# LMS.net
KiCad netlist of a schematic drawn in Altium Designer
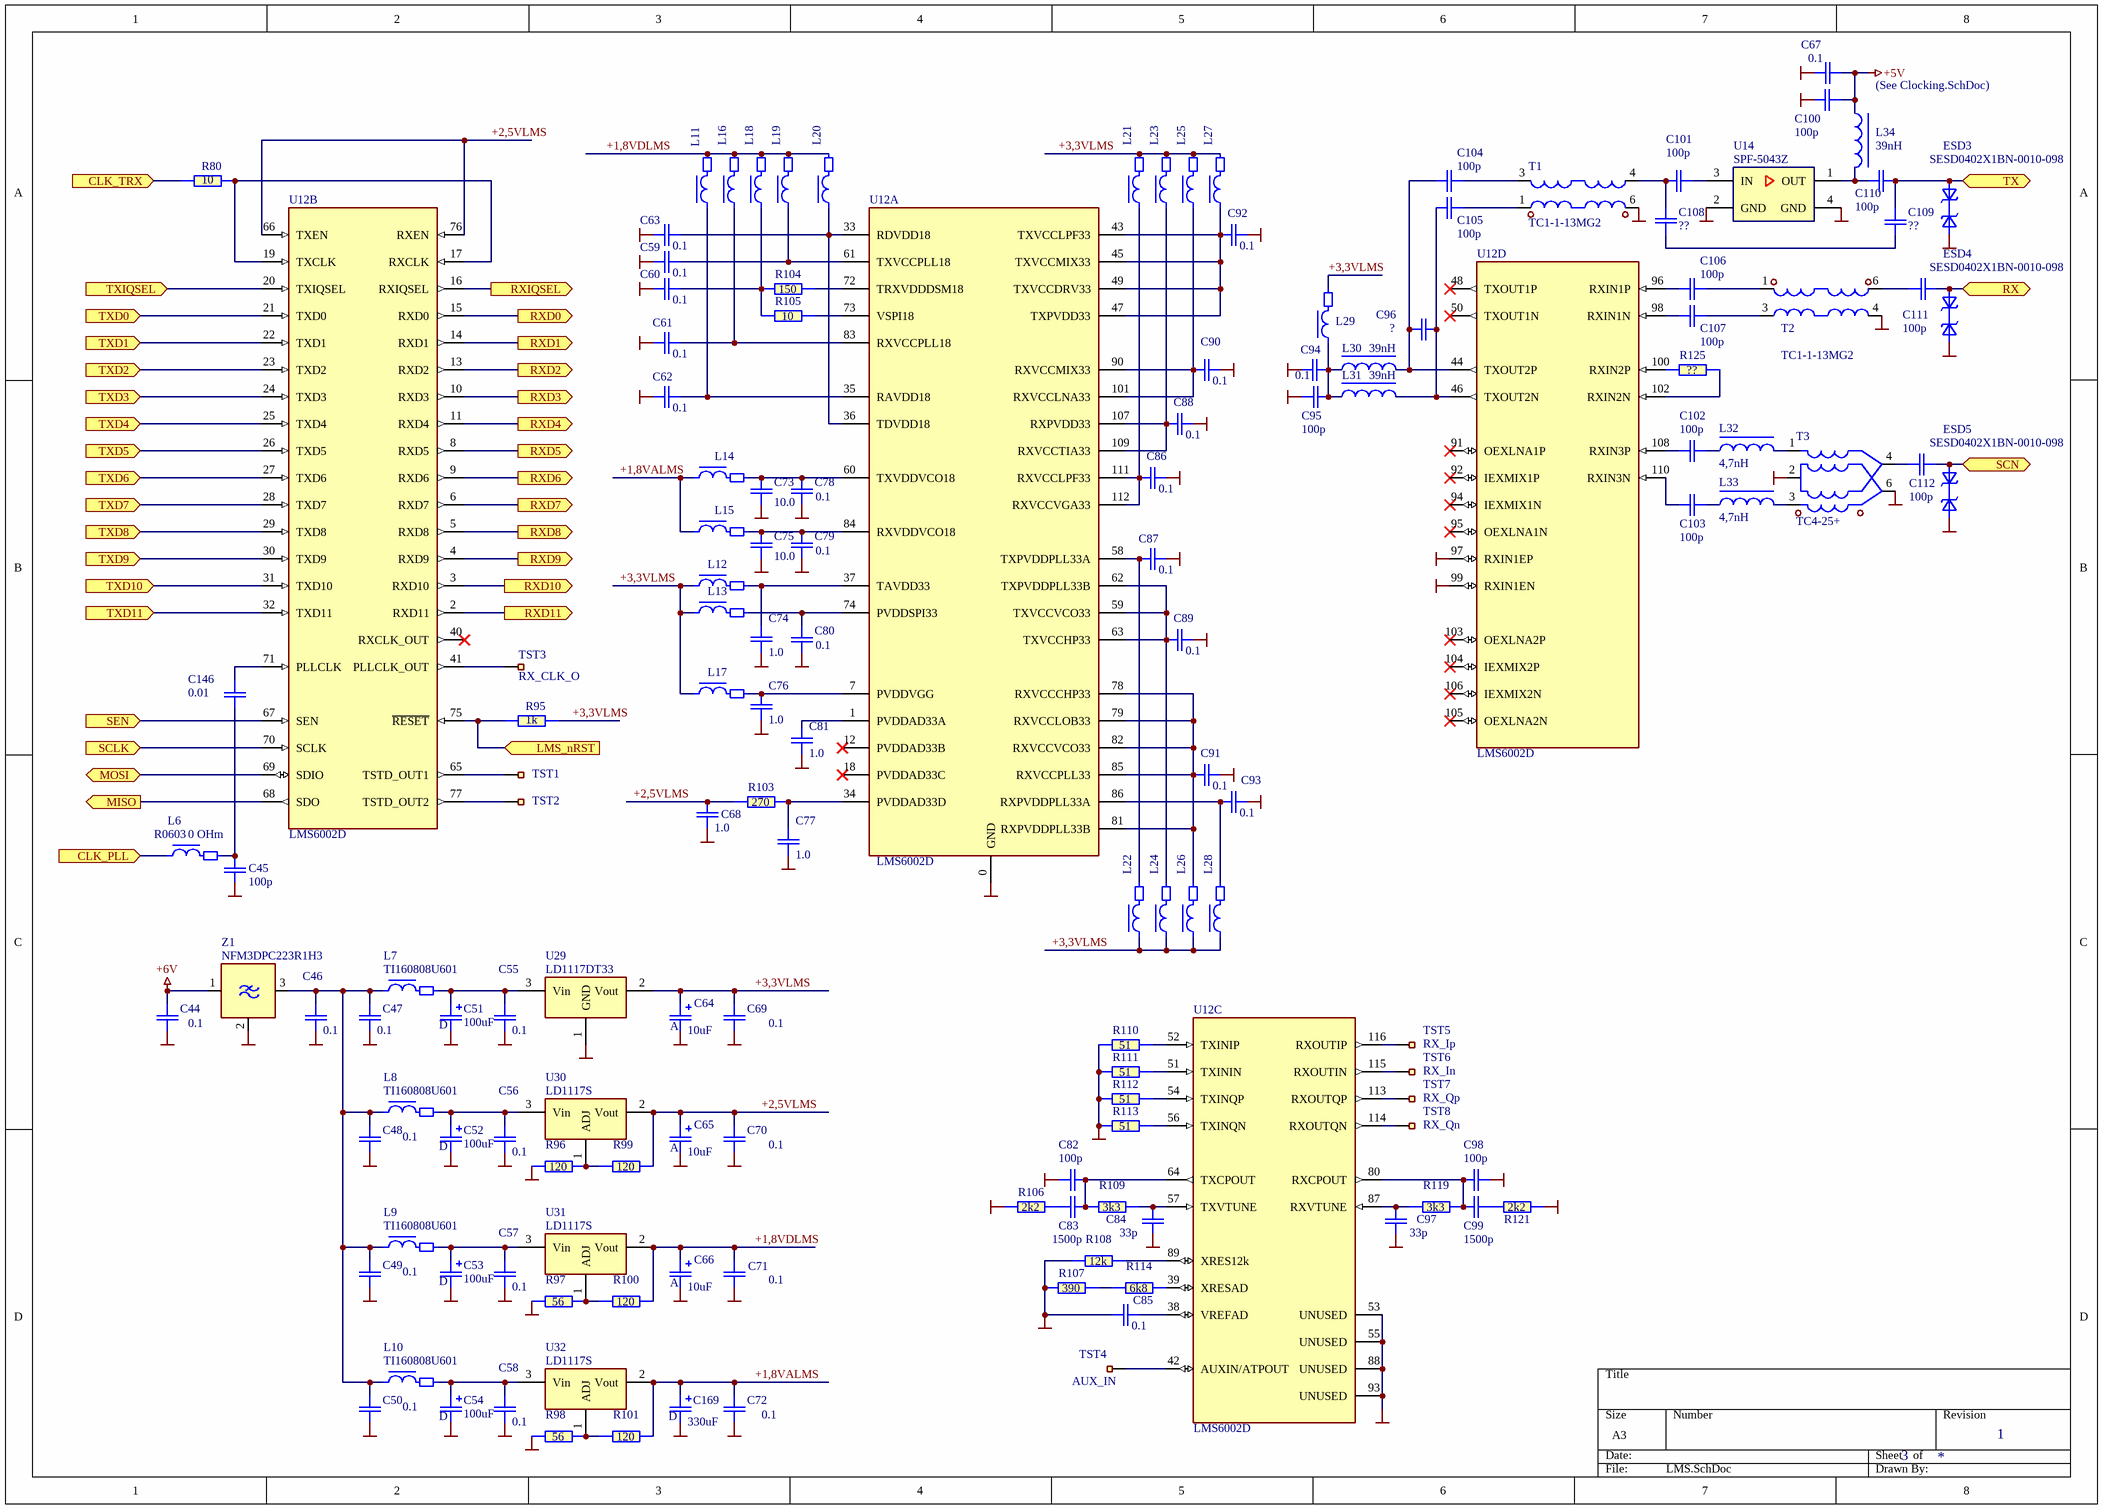
[diagram p0: LMS.SchDoc]

(export (version "E")
  (design (tool "Eeschema 10.0.6"))
  (components
    (comp (ref "C44")
      (value "0.1")
      (footprint "C0402-Phillips")
      (description "Конденсатор")
      (fields (field (name "MANUFACTURER") "MURATA") (field (name "TOLERANCE") "20%"))
      (libsource (lib "Capacitors") (part "C0402"))
    )
    (comp (ref "C45")
      (value "100p")
      (footprint "C0603-PHILLIPS")
      (description "Конденсатор")
      (fields (field (name "MANUFACTURER") "MURATA") (field (name "TOLERANCE") "20%"))
      (libsource (lib "altium-import") (part "root_2_mirrored_C0603_"))
    )
    (comp (ref "C46")
      (value "0.1")
      (footprint "C0402-Phillips")
      (description "Конденсатор")
      (fields (field (name "MANUFACTURER") "MURATA") (field (name "TOLERANCE") "20%"))
      (libsource (lib "Capacitors") (part "C0402"))
    )
    (comp (ref "C47")
      (value "0.1")
      (footprint "C0402-Phillips")
      (description "Конденсатор")
      (fields (field (name "MANUFACTURER") "MURATA") (field (name "TOLERANCE") "20%"))
      (libsource (lib "Capacitors") (part "C0402"))
    )
    (comp (ref "C48")
      (value "0.1")
      (footprint "C0402-Phillips")
      (description "Конденсатор")
      (fields (field (name "MANUFACTURER") "MURATA") (field (name "TOLERANCE") "20%"))
      (libsource (lib "Capacitors") (part "C0402"))
    )
    (comp (ref "C49")
      (value "0.1")
      (footprint "C0402-Phillips")
      (description "Конденсатор")
      (fields (field (name "MANUFACTURER") "MURATA") (field (name "TOLERANCE") "20%"))
      (libsource (lib "Capacitors") (part "C0402"))
    )
    (comp (ref "C50")
      (value "0.1")
      (footprint "C0402-Phillips")
      (description "Конденсатор")
      (fields (field (name "MANUFACTURER") "MURATA") (field (name "TOLERANCE") "20%"))
      (libsource (lib "Capacitors") (part "C0402"))
    )
    (comp (ref "C51")
      (value "100uF")
      (footprint "cd7343")
      (description "Конденсатор")
      (fields (field (name "MANUFACTURER") "SPRAGUE"))
      (libsource (lib "altium-import") (part "root_0_CD7343_"))
    )
    (comp (ref "C52")
      (value "100uF")
      (footprint "cd7343")
      (description "Конденсатор")
      (fields (field (name "MANUFACTURER") "SPRAGUE"))
      (libsource (lib "altium-import") (part "root_0_CD7343_"))
    )
    (comp (ref "C53")
      (value "100uF")
      (footprint "cd7343")
      (description "Конденсатор")
      (fields (field (name "MANUFACTURER") "SPRAGUE"))
      (libsource (lib "altium-import") (part "root_0_CD7343_"))
    )
    (comp (ref "C54")
      (value "100uF")
      (footprint "cd7343")
      (description "Конденсатор")
      (fields (field (name "MANUFACTURER") "SPRAGUE"))
      (libsource (lib "altium-import") (part "root_0_CD7343_"))
    )
    (comp (ref "C55")
      (value "0.1")
      (footprint "C0402-Phillips")
      (description "Конденсатор")
      (fields (field (name "MANUFACTURER") "MURATA") (field (name "TOLERANCE") "20%"))
      (libsource (lib "Capacitors") (part "C0402"))
    )
    (comp (ref "C56")
      (value "0.1")
      (footprint "C0402-Phillips")
      (description "Конденсатор")
      (fields (field (name "MANUFACTURER") "MURATA") (field (name "TOLERANCE") "20%"))
      (libsource (lib "Capacitors") (part "C0402"))
    )
    (comp (ref "C57")
      (value "0.1")
      (footprint "C0402-Phillips")
      (description "Конденсатор")
      (fields (field (name "MANUFACTURER") "MURATA") (field (name "TOLERANCE") "20%"))
      (libsource (lib "Capacitors") (part "C0402"))
    )
    (comp (ref "C58")
      (value "0.1")
      (footprint "C0402-Phillips")
      (description "Конденсатор")
      (fields (field (name "MANUFACTURER") "MURATA") (field (name "TOLERANCE") "20%"))
      (libsource (lib "Capacitors") (part "C0402"))
    )
    (comp (ref "C59")
      (value "0.1")
      (footprint "C0402-Phillips")
      (description "Конденсатор")
      (fields (field (name "MANUFACTURER") "MURATA") (field (name "TOLERANCE") "20%"))
      (libsource (lib "Capacitors") (part "C0402"))
    )
    (comp (ref "C60")
      (value "0.1")
      (footprint "C0402-Phillips")
      (description "Конденсатор")
      (fields (field (name "MANUFACTURER") "MURATA") (field (name "TOLERANCE") "20%"))
      (libsource (lib "Capacitors") (part "C0402"))
    )
    (comp (ref "C61")
      (value "0.1")
      (footprint "C0402-Phillips")
      (description "Конденсатор")
      (fields (field (name "MANUFACTURER") "MURATA") (field (name "TOLERANCE") "20%"))
      (libsource (lib "Capacitors") (part "C0402"))
    )
    (comp (ref "C62")
      (value "0.1")
      (footprint "C0402-Phillips")
      (description "Конденсатор")
      (fields (field (name "MANUFACTURER") "MURATA") (field (name "TOLERANCE") "20%"))
      (libsource (lib "Capacitors") (part "C0402"))
    )
    (comp (ref "C63")
      (value "0.1")
      (footprint "C0402-Phillips")
      (description "Конденсатор")
      (fields (field (name "MANUFACTURER") "MURATA") (field (name "TOLERANCE") "20%"))
      (libsource (lib "Capacitors") (part "C0402"))
    )
    (comp (ref "C64")
      (value "10uF")
      (footprint "CA3216")
      (description "Конденсатор")
      (fields (field (name "MANUFACTURER") "SPRAGUE"))
      (libsource (lib "Capacitors") (part "CA3216"))
    )
    (comp (ref "C65")
      (value "10uF")
      (footprint "CA3216")
      (description "Конденсатор")
      (fields (field (name "MANUFACTURER") "SPRAGUE"))
      (libsource (lib "Capacitors") (part "CA3216"))
    )
    (comp (ref "C66")
      (value "10uF")
      (footprint "CA3216")
      (description "Конденсатор")
      (fields (field (name "MANUFACTURER") "SPRAGUE"))
      (libsource (lib "Capacitors") (part "CA3216"))
    )
    (comp (ref "C67")
      (value "0.1")
      (footprint "C0402-Phillips")
      (description "Конденсатор")
      (fields (field (name "MANUFACTURER") "MURATA") (field (name "TOLERANCE") "20%"))
      (libsource (lib "Capacitors") (part "C0402"))
    )
    (comp (ref "C68")
      (value "1.0")
      (footprint "C0603-PHILLIPS")
      (description "Конденсатор")
      (fields (field (name "MANUFACTURER") "MURATA") (field (name "TOLERANCE") "20%"))
      (libsource (lib "altium-import") (part "root_0_C0603_"))
    )
    (comp (ref "C69")
      (value "0.1")
      (footprint "C0402-Phillips")
      (description "Конденсатор")
      (fields (field (name "MANUFACTURER") "MURATA") (field (name "TOLERANCE") "20%"))
      (libsource (lib "Capacitors") (part "C0402"))
    )
    (comp (ref "C70")
      (value "0.1")
      (footprint "C0402-Phillips")
      (description "Конденсатор")
      (fields (field (name "MANUFACTURER") "MURATA") (field (name "TOLERANCE") "20%"))
      (libsource (lib "Capacitors") (part "C0402"))
    )
    (comp (ref "C71")
      (value "0.1")
      (footprint "C0402-Phillips")
      (description "Конденсатор")
      (fields (field (name "MANUFACTURER") "MURATA") (field (name "TOLERANCE") "20%"))
      (libsource (lib "Capacitors") (part "C0402"))
    )
    (comp (ref "C72")
      (value "0.1")
      (footprint "C0402-Phillips")
      (description "Конденсатор")
      (fields (field (name "MANUFACTURER") "MURATA") (field (name "TOLERANCE") "20%"))
      (libsource (lib "Capacitors") (part "C0402"))
    )
    (comp (ref "C73")
      (value "10.0")
      (footprint "C0603-Phillips")
      (description "Конденсатор")
      (fields (field (name "MANUFACTURER") "MURATA") (field (name "TOLERANCE") "20%"))
      (libsource (lib "Capacitors") (part "C0603"))
    )
    (comp (ref "C74")
      (value "1.0")
      (footprint "C0603-PHILLIPS")
      (description "Конденсатор")
      (fields (field (name "MANUFACTURER") "MURATA") (field (name "TOLERANCE") "20%"))
      (libsource (lib "altium-import") (part "root_0_C0603_"))
    )
    (comp (ref "C75")
      (value "10.0")
      (footprint "C0603-Phillips")
      (description "Конденсатор")
      (fields (field (name "MANUFACTURER") "MURATA") (field (name "TOLERANCE") "20%"))
      (libsource (lib "Capacitors") (part "C0603"))
    )
    (comp (ref "C76")
      (value "1.0")
      (footprint "C0603-PHILLIPS")
      (description "Конденсатор")
      (fields (field (name "MANUFACTURER") "MURATA") (field (name "TOLERANCE") "20%"))
      (libsource (lib "altium-import") (part "root_0_C0603_"))
    )
    (comp (ref "C77")
      (value "1.0")
      (footprint "C0603-PHILLIPS")
      (description "Конденсатор")
      (fields (field (name "MANUFACTURER") "MURATA") (field (name "TOLERANCE") "20%"))
      (libsource (lib "altium-import") (part "root_0_C0603_"))
    )
    (comp (ref "C78")
      (value "0.1")
      (footprint "C0402-Phillips")
      (description "Конденсатор")
      (fields (field (name "MANUFACTURER") "MURATA") (field (name "TOLERANCE") "20%"))
      (libsource (lib "Capacitors") (part "C0402"))
    )
    (comp (ref "C79")
      (value "0.1")
      (footprint "C0402-cirq")
      (description "Конденсатор")
      (fields (field (name "MANUFACTURER") "MURATA") (field (name "TOLERANCE") "20%"))
      (libsource (lib "Capacitors") (part "C0402"))
    )
    (comp (ref "C80")
      (value "0.1")
      (footprint "C0402-cirq")
      (description "Конденсатор")
      (fields (field (name "MANUFACTURER") "MURATA") (field (name "TOLERANCE") "20%"))
      (libsource (lib "Capacitors") (part "C0402"))
    )
    (comp (ref "C81")
      (value "1.0")
      (footprint "C0603-PHILLIPS")
      (description "Конденсатор")
      (fields (field (name "MANUFACTURER") "MURATA") (field (name "TOLERANCE") "20%"))
      (libsource (lib "altium-import") (part "root_0_C0603_"))
    )
    (comp (ref "C82")
      (value "100p")
      (footprint "C0603-PHILLIPS")
      (description "Конденсатор")
      (fields (field (name "MANUFACTURER") "MURATA") (field (name "TOLERANCE") "20%"))
      (libsource (lib "altium-import") (part "root_1_mirrored_C0603_"))
    )
    (comp (ref "C83")
      (value "1500p")
      (footprint "C0603-PHILLIPS")
      (description "Конденсатор")
      (fields (field (name "MANUFACTURER") "MURATA") (field (name "TOLERANCE") "20%"))
      (libsource (lib "altium-import") (part "root_1_mirrored_C0603_"))
    )
    (comp (ref "C84")
      (value "33p")
      (footprint "C0603-PHILLIPS")
      (description "Конденсатор")
      (fields (field (name "MANUFACTURER") "MURATA") (field (name "TOLERANCE") "20%"))
      (libsource (lib "altium-import") (part "root_2_mirrored_C0603_"))
    )
    (comp (ref "C85")
      (value "0.1")
      (footprint "C0402-Phillips")
      (description "Конденсатор")
      (fields (field (name "MANUFACTURER") "MURATA") (field (name "TOLERANCE") "20%"))
      (libsource (lib "Capacitors") (part "C0402"))
    )
    (comp (ref "C86")
      (value "0.1")
      (footprint "C0402-Phillips")
      (description "Конденсатор")
      (fields (field (name "MANUFACTURER") "MURATA") (field (name "TOLERANCE") "20%"))
      (libsource (lib "Capacitors") (part "C0402"))
    )
    (comp (ref "C87")
      (value "0.1")
      (footprint "C0402-Phillips")
      (description "Конденсатор")
      (fields (field (name "MANUFACTURER") "MURATA") (field (name "TOLERANCE") "20%"))
      (libsource (lib "Capacitors") (part "C0402"))
    )
    (comp (ref "C88")
      (value "0.1")
      (footprint "C0402-cirq")
      (description "Конденсатор")
      (fields (field (name "MANUFACTURER") "MURATA") (field (name "TOLERANCE") "20%"))
      (libsource (lib "Capacitors") (part "C0402"))
    )
    (comp (ref "C89")
      (value "0.1")
      (footprint "C0402-cirq")
      (description "Конденсатор")
      (fields (field (name "MANUFACTURER") "MURATA") (field (name "TOLERANCE") "20%"))
      (libsource (lib "Capacitors") (part "C0402"))
    )
    (comp (ref "C90")
      (value "0.1")
      (footprint "C0402-Phillips")
      (description "Конденсатор")
      (fields (field (name "MANUFACTURER") "MURATA") (field (name "TOLERANCE") "20%"))
      (libsource (lib "Capacitors") (part "C0402"))
    )
    (comp (ref "C91")
      (value "0.1")
      (footprint "C0402-Phillips")
      (description "Конденсатор")
      (fields (field (name "MANUFACTURER") "MURATA") (field (name "TOLERANCE") "20%"))
      (libsource (lib "Capacitors") (part "C0402"))
    )
    (comp (ref "C92")
      (value "0.1")
      (footprint "C0402-cirq")
      (description "Конденсатор")
      (fields (field (name "MANUFACTURER") "MURATA") (field (name "TOLERANCE") "20%"))
      (libsource (lib "Capacitors") (part "C0402"))
    )
    (comp (ref "C93")
      (value "0.1")
      (footprint "C0402-Phillips")
      (description "Конденсатор")
      (fields (field (name "MANUFACTURER") "MURATA") (field (name "TOLERANCE") "20%"))
      (libsource (lib "Capacitors") (part "C0402"))
    )
    (comp (ref "C94")
      (value "0.1")
      (footprint "C0402-Phillips")
      (description "Конденсатор")
      (fields (field (name "MANUFACTURER") "MURATA") (field (name "TOLERANCE") "20%"))
      (libsource (lib "Capacitors") (part "C0402"))
    )
    (comp (ref "C95")
      (value "100p")
      (footprint "C0603-PHILLIPS")
      (description "Конденсатор")
      (fields (field (name "MANUFACTURER") "MURATA") (field (name "TOLERANCE") "20%"))
      (libsource (lib "altium-import") (part "root_3_C0603_"))
    )
    (comp (ref "C96")
      (value "?")
      (footprint "C0603-PHILLIPS")
      (description "Конденсатор")
      (fields (field (name "MANUFACTURER") "MURATA") (field (name "TOLERANCE") "20%"))
      (libsource (lib "altium-import") (part "root_3_C0603_"))
    )
    (comp (ref "C97")
      (value "33p")
      (footprint "C0603-PHILLIPS")
      (description "Конденсатор")
      (fields (field (name "MANUFACTURER") "MURATA") (field (name "TOLERANCE") "20%"))
      (libsource (lib "altium-import") (part "root_2_C0603_"))
    )
    (comp (ref "C98")
      (value "100p")
      (footprint "C0603-PHILLIPS")
      (description "Конденсатор")
      (fields (field (name "MANUFACTURER") "MURATA") (field (name "TOLERANCE") "20%"))
      (libsource (lib "altium-import") (part "root_1_C0603_"))
    )
    (comp (ref "C99")
      (value "1500p")
      (footprint "C0603-PHILLIPS")
      (description "Конденсатор")
      (fields (field (name "MANUFACTURER") "MURATA") (field (name "TOLERANCE") "20%"))
      (libsource (lib "altium-import") (part "root_1_C0603_"))
    )
    (comp (ref "C100")
      (value "100p")
      (footprint "C0603-PHILLIPS")
      (description "Конденсатор")
      (fields (field (name "MANUFACTURER") "MURATA") (field (name "TOLERANCE") "20%"))
      (libsource (lib "altium-import") (part "root_1_C0603_"))
    )
    (comp (ref "C101")
      (value "100p")
      (footprint "C0603-PHILLIPS")
      (description "Конденсатор")
      (fields (field (name "MANUFACTURER") "MURATA") (field (name "TOLERANCE") "20%"))
      (libsource (lib "altium-import") (part "root_1_C0603_"))
    )
    (comp (ref "C102")
      (value "100p")
      (footprint "C0603-PHILLIPS")
      (description "Конденсатор")
      (fields (field (name "MANUFACTURER") "MURATA") (field (name "TOLERANCE") "20%"))
      (libsource (lib "altium-import") (part "root_1_C0603_"))
    )
    (comp (ref "C103")
      (value "100p")
      (footprint "C0603-PHILLIPS")
      (description "Конденсатор")
      (fields (field (name "MANUFACTURER") "MURATA") (field (name "TOLERANCE") "20%"))
      (libsource (lib "altium-import") (part "root_1_C0603_"))
    )
    (comp (ref "C104")
      (value "100p")
      (footprint "C0603-PHILLIPS")
      (description "Конденсатор")
      (fields (field (name "MANUFACTURER") "MURATA") (field (name "TOLERANCE") "20%"))
      (libsource (lib "altium-import") (part "root_1_C0603_"))
    )
    (comp (ref "C105")
      (value "100p")
      (footprint "C0603-PHILLIPS")
      (description "Конденсатор")
      (fields (field (name "MANUFACTURER") "MURATA") (field (name "TOLERANCE") "20%"))
      (libsource (lib "altium-import") (part "root_1_C0603_"))
    )
    (comp (ref "C106")
      (value "100p")
      (footprint "C0603-PHILLIPS")
      (description "Конденсатор")
      (fields (field (name "MANUFACTURER") "MURATA") (field (name "TOLERANCE") "20%"))
      (libsource (lib "altium-import") (part "root_1_C0603_"))
    )
    (comp (ref "C107")
      (value "100p")
      (footprint "C0603-PHILLIPS")
      (description "Конденсатор")
      (fields (field (name "MANUFACTURER") "MURATA") (field (name "TOLERANCE") "20%"))
      (libsource (lib "altium-import") (part "root_1_C0603_"))
    )
    (comp (ref "C108")
      (value "??")
      (footprint "C0603-PHILLIPS")
      (description "Конденсатор")
      (fields (field (name "MANUFACTURER") "MURATA") (field (name "TOLERANCE") "20%"))
      (libsource (lib "altium-import") (part "root_0_C0603_"))
    )
    (comp (ref "C109")
      (value "??")
      (footprint "C0603-PHILLIPS")
      (description "Конденсатор")
      (fields (field (name "MANUFACTURER") "MURATA") (field (name "TOLERANCE") "20%"))
      (libsource (lib "altium-import") (part "root_2_C0603_"))
    )
    (comp (ref "C110")
      (value "100p")
      (footprint "C0603-PHILLIPS")
      (description "Конденсатор")
      (fields (field (name "MANUFACTURER") "MURATA") (field (name "TOLERANCE") "20%"))
      (libsource (lib "altium-import") (part "root_1_C0603_"))
    )
    (comp (ref "C111")
      (value "100p")
      (footprint "C0603-PHILLIPS")
      (description "Конденсатор")
      (fields (field (name "MANUFACTURER") "MURATA") (field (name "TOLERANCE") "20%"))
      (libsource (lib "altium-import") (part "root_3_C0603_"))
    )
    (comp (ref "C112")
      (value "100p")
      (footprint "C0603-PHILLIPS")
      (description "Конденсатор")
      (fields (field (name "MANUFACTURER") "MURATA") (field (name "TOLERANCE") "20%"))
      (libsource (lib "altium-import") (part "root_1_C0603_"))
    )
    (comp (ref "C146")
      (value "0.01")
      (footprint "C0603-PHILLIPS")
      (description "Конденсатор")
      (fields (field (name "MANUFACTURER") "MURATA") (field (name "TOLERANCE") "20%"))
      (libsource (lib "altium-import") (part "root_2_mirrored_C0603_"))
    )
    (comp (ref "C169")
      (value "330uF")
      (footprint "cd7343")
      (description "Конденсатор")
      (fields (field (name "MANUFACTURER") "Kemet"))
      (libsource (lib "altium-import") (part "root_0_CD7343_"))
    )
    (comp (ref "ESD3")
      (value "SESD0402X1BN-0010-098")
      (footprint "R0402-Phillips")
      (description "ESD diod bi-directional")
      (fields (field (name "MANUFACTURER") "Tyco Electronics Corp"))
      (libsource (lib "*") (part "SESD0402X"))
    )
    (comp (ref "ESD4")
      (value "SESD0402X1BN-0010-098")
      (footprint "R0402-Phillips")
      (description "ESD diod bi-directional")
      (fields (field (name "MANUFACTURER") "Tyco Electronics Corp"))
      (libsource (lib "*") (part "SESD0402X"))
    )
    (comp (ref "ESD5")
      (value "SESD0402X1BN-0010-098")
      (footprint "R0402-Phillips")
      (description "ESD diod bi-directional")
      (fields (field (name "MANUFACTURER") "Tyco Electronics Corp"))
      (libsource (lib "*") (part "SESD0402X"))
    )
    (comp (ref "L6")
      (value "R0603")
      (footprint "Andy:Ti160808-Phillips")
      (description "Дроссель ЭМС")
      (fields (field (name "MANUFACTURER") "MURATA") (field (name "ALTIUM_VALUE") "0 OHm"))
      (libsource (lib "altium-import") (part "root_0_TI160808_"))
    )
    (comp (ref "L7")
      (value "TI160808U601")
      (footprint "Andy:Ti160808-Phillips")
      (description "Дроссель ЭМС")
      (fields (field (name "MANUFACTURER") "MURATA"))
      (libsource (lib "altium-import") (part "root_0_TI160808_"))
    )
    (comp (ref "L8")
      (value "TI160808U601")
      (footprint "Andy:Ti160808-Phillips")
      (description "Дроссель ЭМС")
      (fields (field (name "MANUFACTURER") "MURATA"))
      (libsource (lib "altium-import") (part "root_0_TI160808_"))
    )
    (comp (ref "L9")
      (value "TI160808U601")
      (footprint "Andy:Ti160808-Phillips")
      (description "Дроссель ЭМС")
      (fields (field (name "MANUFACTURER") "MURATA"))
      (libsource (lib "altium-import") (part "root_0_TI160808_"))
    )
    (comp (ref "L10")
      (value "TI160808U601")
      (footprint "Andy:Ti160808-Phillips")
      (description "Дроссель ЭМС")
      (fields (field (name "MANUFACTURER") "MURATA"))
      (libsource (lib "altium-import") (part "root_0_TI160808_"))
    )
    (comp (ref "L11")
      (value "TI160808U601")
      (footprint "Andy:Ti160808-Phillips")
      (description "Дроссель ЭМС")
      (fields (field (name "MANUFACTURER") "MURATA"))
      (libsource (lib "altium-import") (part "root_1_TI160808_"))
    )
    (comp (ref "L12")
      (value "TI160808U601")
      (footprint "Andy:Ti160808-Phillips")
      (description "Дроссель ЭМС")
      (fields (field (name "MANUFACTURER") "MURATA"))
      (libsource (lib "altium-import") (part "root_0_TI160808_"))
    )
    (comp (ref "L13")
      (value "TI160808U601")
      (footprint "Andy:Ti160808-Phillips")
      (description "Дроссель ЭМС")
      (fields (field (name "MANUFACTURER") "MURATA"))
      (libsource (lib "altium-import") (part "root_0_TI160808_"))
    )
    (comp (ref "L14")
      (value "TI160808U601")
      (footprint "Andy:Ti160808-Phillips")
      (description "Дроссель ЭМС")
      (fields (field (name "MANUFACTURER") "MURATA"))
      (libsource (lib "altium-import") (part "root_0_TI160808_"))
    )
    (comp (ref "L15")
      (value "TI160808U601")
      (footprint "Andy:Ti160808-Phillips")
      (description "Дроссель ЭМС")
      (fields (field (name "MANUFACTURER") "MURATA"))
      (libsource (lib "altium-import") (part "root_0_TI160808_"))
    )
    (comp (ref "L16")
      (value "TI160808U601")
      (footprint "Andy:Ti160808-Phillips")
      (description "Дроссель ЭМС")
      (fields (field (name "MANUFACTURER") "MURATA"))
      (libsource (lib "altium-import") (part "root_1_TI160808_"))
    )
    (comp (ref "L17")
      (value "TI160808U601")
      (footprint "Andy:Ti160808-Phillips")
      (description "Дроссель ЭМС")
      (fields (field (name "MANUFACTURER") "MURATA"))
      (libsource (lib "altium-import") (part "root_0_TI160808_"))
    )
    (comp (ref "L18")
      (value "TI160808U601")
      (footprint "Andy:Ti160808-Phillips")
      (description "Дроссель ЭМС")
      (fields (field (name "MANUFACTURER") "MURATA"))
      (libsource (lib "altium-import") (part "root_1_TI160808_"))
    )
    (comp (ref "L19")
      (value "TI160808U601")
      (footprint "Andy:Ti160808-Phillips")
      (description "Дроссель ЭМС")
      (fields (field (name "MANUFACTURER") "MURATA"))
      (libsource (lib "altium-import") (part "root_1_TI160808_"))
    )
    (comp (ref "L20")
      (value "TI160808U601")
      (footprint "Andy:Ti160808-Phillips")
      (description "Дроссель ЭМС")
      (fields (field (name "MANUFACTURER") "MURATA"))
      (libsource (lib "altium-import") (part "root_1_TI160808_"))
    )
    (comp (ref "L21")
      (value "TI160808U601")
      (footprint "Andy:Ti160808-Phillips")
      (description "Дроссель ЭМС")
      (fields (field (name "MANUFACTURER") "MURATA"))
      (libsource (lib "altium-import") (part "root_1_TI160808_"))
    )
    (comp (ref "L22")
      (value "TI160808U601")
      (footprint "Andy:Ti160808-Phillips")
      (description "Дроссель ЭМС")
      (fields (field (name "MANUFACTURER") "MURATA"))
      (libsource (lib "altium-import") (part "root_1_TI160808_"))
    )
    (comp (ref "L23")
      (value "TI160808U601")
      (footprint "Andy:Ti160808-Phillips")
      (description "Дроссель ЭМС")
      (fields (field (name "MANUFACTURER") "MURATA"))
      (libsource (lib "altium-import") (part "root_1_TI160808_"))
    )
    (comp (ref "L24")
      (value "TI160808U601")
      (footprint "Andy:Ti160808-Phillips")
      (description "Дроссель ЭМС")
      (fields (field (name "MANUFACTURER") "MURATA"))
      (libsource (lib "altium-import") (part "root_1_TI160808_"))
    )
    (comp (ref "L25")
      (value "TI160808U601")
      (footprint "Andy:Ti160808-Phillips")
      (description "Дроссель ЭМС")
      (fields (field (name "MANUFACTURER") "MURATA"))
      (libsource (lib "altium-import") (part "root_1_TI160808_"))
    )
    (comp (ref "L26")
      (value "TI160808U601")
      (footprint "Andy:Ti160808-Phillips")
      (description "Дроссель ЭМС")
      (fields (field (name "MANUFACTURER") "MURATA"))
      (libsource (lib "altium-import") (part "root_1_TI160808_"))
    )
    (comp (ref "L27")
      (value "TI160808U601")
      (footprint "Andy:Ti160808-Phillips")
      (description "Дроссель ЭМС")
      (fields (field (name "MANUFACTURER") "MURATA"))
      (libsource (lib "altium-import") (part "root_1_TI160808_"))
    )
    (comp (ref "L28")
      (value "TI160808U601")
      (footprint "Andy:Ti160808-Phillips")
      (description "Дроссель ЭМС")
      (fields (field (name "MANUFACTURER") "MURATA"))
      (libsource (lib "altium-import") (part "root_1_TI160808_"))
    )
    (comp (ref "L29")
      (value "TI160808U601")
      (footprint "Andy:Ti160808-Phillips")
      (description "Дроссель ЭМС")
      (fields (field (name "MANUFACTURER") "MURATA"))
      (libsource (lib "altium-import") (part "root_1_TI160808_"))
    )
    (comp (ref "L30")
      (value "39nH")
      (footprint "Andy:TF160808-Phillips")
      (description "Индуктивность")
      (fields (field (name "MANUFACTURER") "SMD"))
      (libsource (lib "altium-import") (part "root_0_TF160808_"))
    )
    (comp (ref "L31")
      (value "39nH")
      (footprint "Andy:TF160808-Phillips")
      (description "Индуктивность")
      (fields (field (name "MANUFACTURER") "SMD"))
      (libsource (lib "altium-import") (part "root_0_TF160808_"))
    )
    (comp (ref "L32")
      (value "4,7nH")
      (footprint "Andy:TF160808-Phillips")
      (description "Индуктивность")
      (fields (field (name "MANUFACTURER") "SMD"))
      (libsource (lib "altium-import") (part "root_0_TF160808_"))
    )
    (comp (ref "L33")
      (value "4,7nH")
      (footprint "Andy:TF160808-Phillips")
      (description "Индуктивность")
      (fields (field (name "MANUFACTURER") "SMD"))
      (libsource (lib "altium-import") (part "root_0_TF160808_"))
    )
    (comp (ref "L34")
      (value "39nH")
      (footprint "Andy:TF160808-Phillips")
      (description "Индуктивность")
      (fields (field (name "MANUFACTURER") "SMD"))
      (libsource (lib "altium-import") (part "root_3_TF160808_"))
    )
    (comp (ref "R80")
      (value "10")
      (footprint "R0603-PHILLIPS")
      (description "Резистор")
      (fields (field (name "MANUFACTURER") "YAGEO") (field (name "TOLERANCE") "5%"))
      (libsource (lib "altium-import") (part "root_1_R0603_"))
    )
    (comp (ref "R95")
      (value "1k")
      (footprint "R0603-PHILLIPS")
      (description "Резистор")
      (fields (field (name "MANUFACTURER") "YAGEO") (field (name "TOLERANCE") "5%"))
      (libsource (lib "altium-import") (part "root_1_R0603_"))
    )
    (comp (ref "R96")
      (value "120")
      (footprint "R0603-PHILLIPS")
      (description "Резистор")
      (fields (field (name "MANUFACTURER") "YAGEO") (field (name "TOLERANCE") "5%"))
      (libsource (lib "altium-import") (part "root_1_R0603_"))
    )
    (comp (ref "R97")
      (value "56")
      (footprint "R0603-PHILLIPS")
      (description "Резистор")
      (fields (field (name "MANUFACTURER") "YAGEO") (field (name "TOLERANCE") "5%"))
      (libsource (lib "altium-import") (part "root_1_R0603_"))
    )
    (comp (ref "R98")
      (value "56")
      (footprint "R0603-PHILLIPS")
      (description "Резистор")
      (fields (field (name "MANUFACTURER") "YAGEO") (field (name "TOLERANCE") "5%"))
      (libsource (lib "altium-import") (part "root_1_R0603_"))
    )
    (comp (ref "R99")
      (value "120")
      (footprint "R0603-PHILLIPS")
      (description "Резистор")
      (fields (field (name "MANUFACTURER") "YAGEO") (field (name "TOLERANCE") "5%"))
      (libsource (lib "altium-import") (part "root_1_R0603_"))
    )
    (comp (ref "R100")
      (value "120")
      (footprint "R0603-PHILLIPS")
      (description "Резистор")
      (fields (field (name "MANUFACTURER") "YAGEO") (field (name "TOLERANCE") "5%"))
      (libsource (lib "altium-import") (part "root_1_R0603_"))
    )
    (comp (ref "R101")
      (value "120")
      (footprint "R0603-PHILLIPS")
      (description "Резистор")
      (fields (field (name "MANUFACTURER") "YAGEO") (field (name "TOLERANCE") "5%"))
      (libsource (lib "altium-import") (part "root_1_R0603_"))
    )
    (comp (ref "R103")
      (value "270")
      (footprint "R0603-PHILLIPS")
      (description "Резистор")
      (fields (field (name "MANUFACTURER") "YAGEO") (field (name "TOLERANCE") "5%"))
      (libsource (lib "altium-import") (part "root_1_R0603_"))
    )
    (comp (ref "R104")
      (value "150")
      (footprint "R0603-PHILLIPS")
      (description "Резистор")
      (fields (field (name "MANUFACTURER") "YAGEO") (field (name "TOLERANCE") "5%"))
      (libsource (lib "altium-import") (part "root_1_R0603_"))
    )
    (comp (ref "R105")
      (value "10")
      (footprint "R0603-PHILLIPS")
      (description "Резистор")
      (fields (field (name "MANUFACTURER") "YAGEO") (field (name "TOLERANCE") "5%"))
      (libsource (lib "altium-import") (part "root_1_R0603_"))
    )
    (comp (ref "R106")
      (value "2k2")
      (footprint "R0603-PHILLIPS")
      (description "Резистор")
      (fields (field (name "MANUFACTURER") "YAGEO") (field (name "TOLERANCE") "5%"))
      (libsource (lib "altium-import") (part "root_1_R0603_"))
    )
    (comp (ref "R107")
      (value "390")
      (footprint "R0603-PHILLIPS")
      (description "Резистор")
      (fields (field (name "MANUFACTURER") "YAGEO") (field (name "TOLERANCE") "5%"))
      (libsource (lib "altium-import") (part "root_1_R0603_"))
    )
    (comp (ref "R108")
      (value "12k")
      (footprint "R0603-PHILLIPS")
      (description "Резистор")
      (fields (field (name "MANUFACTURER") "YAGEO") (field (name "TOLERANCE") "5%"))
      (libsource (lib "altium-import") (part "root_1_R0603_"))
    )
    (comp (ref "R109")
      (value "3k3")
      (footprint "R0603-PHILLIPS")
      (description "Резистор")
      (fields (field (name "MANUFACTURER") "YAGEO") (field (name "TOLERANCE") "5%"))
      (libsource (lib "altium-import") (part "root_1_R0603_"))
    )
    (comp (ref "R110")
      (value "51")
      (footprint "R0603-PHILLIPS")
      (description "Резистор")
      (fields (field (name "MANUFACTURER") "YAGEO") (field (name "TOLERANCE") "5%"))
      (libsource (lib "altium-import") (part "root_1_R0603_"))
    )
    (comp (ref "R111")
      (value "51")
      (footprint "R0603-PHILLIPS")
      (description "Резистор")
      (fields (field (name "MANUFACTURER") "YAGEO") (field (name "TOLERANCE") "5%"))
      (libsource (lib "altium-import") (part "root_1_R0603_"))
    )
    (comp (ref "R112")
      (value "51")
      (footprint "R0603-PHILLIPS")
      (description "Резистор")
      (fields (field (name "MANUFACTURER") "YAGEO") (field (name "TOLERANCE") "5%"))
      (libsource (lib "altium-import") (part "root_1_R0603_"))
    )
    (comp (ref "R113")
      (value "51")
      (footprint "R0603-PHILLIPS")
      (description "Резистор")
      (fields (field (name "MANUFACTURER") "YAGEO") (field (name "TOLERANCE") "5%"))
      (libsource (lib "altium-import") (part "root_1_R0603_"))
    )
    (comp (ref "R114")
      (value "6k8")
      (footprint "R0603-PHILLIPS")
      (description "Резистор")
      (fields (field (name "MANUFACTURER") "YAGEO") (field (name "TOLERANCE") "5%"))
      (libsource (lib "altium-import") (part "root_1_R0603_"))
    )
    (comp (ref "R119")
      (value "3k3")
      (footprint "R0603-PHILLIPS")
      (description "Резистор")
      (fields (field (name "MANUFACTURER") "YAGEO") (field (name "TOLERANCE") "5%"))
      (libsource (lib "altium-import") (part "root_1_R0603_"))
    )
    (comp (ref "R121")
      (value "2k2")
      (footprint "R0603-PHILLIPS")
      (description "Резистор")
      (fields (field (name "MANUFACTURER") "YAGEO") (field (name "TOLERANCE") "5%"))
      (libsource (lib "altium-import") (part "root_1_R0603_"))
    )
    (comp (ref "R125")
      (value "??")
      (footprint "R0603-PHILLIPS")
      (description "Резистор")
      (fields (field (name "MANUFACTURER") "YAGEO") (field (name "TOLERANCE") "5%"))
      (libsource (lib "altium-import") (part "root_1_R0603_"))
    )
    (comp (ref "T1")
      (value "TC1-1-13MG2")
      (footprint "AT224-1")
      (description "Трансформатор")
      (fields (field (name "MANUFACTURER") "Mini-Cirquits"))
      (libsource (lib "Inductance Transformers") (part "TC1-1-13"))
    )
    (comp (ref "T2")
      (value "TC1-1-13MG2")
      (footprint "AT224-1")
      (description "Трансформатор")
      (fields (field (name "MANUFACTURER") "Mini-Cirquits"))
      (libsource (lib "") (part "TC1-1-13_1"))
    )
    (comp (ref "T3")
      (value "TC4-25+")
      (footprint "AT224-1")
      (description "Трансформатор")
      (fields (field (name "MANUFACTURER") "Mini-Cirquits"))
      (libsource (lib "Inductance Transformers") (part "TC4-25"))
    )
    (comp (ref "TST1")
      (value "~")
      (footprint "kp40x40")
      (description "Контактна  площадка")
      (fields (field (name "MANUFACTURER") "Конструктив"))
      (libsource (lib "Connectors") (part "KP"))
    )
    (comp (ref "TST2")
      (value "~")
      (footprint "kp40x40")
      (description "Контактна  площадка")
      (fields (field (name "MANUFACTURER") "Конструктив"))
      (libsource (lib "Connectors") (part "KP"))
    )
    (comp (ref "TST3")
      (value "RX_CLK_O")
      (footprint "kp40x40")
      (description "Контактна  площадка")
      (fields (field (name "MANUFACTURER") "Конструктив"))
      (libsource (lib "Connectors") (part "KP"))
    )
    (comp (ref "TST4")
      (value "AUX_IN")
      (footprint "kp40x40")
      (description "Контактна  площадка")
      (fields (field (name "MANUFACTURER") "Конструктив"))
      (libsource (lib "") (part "KP_1"))
    )
    (comp (ref "TST5")
      (value "RX_Ip")
      (footprint "kp40x40")
      (description "Контактна  площадка")
      (fields (field (name "MANUFACTURER") "Конструктив"))
      (libsource (lib "Connectors") (part "KP"))
    )
    (comp (ref "TST6")
      (value "RX_In")
      (footprint "kp40x40")
      (description "Контактна  площадка")
      (fields (field (name "MANUFACTURER") "Конструктив"))
      (libsource (lib "Connectors") (part "KP"))
    )
    (comp (ref "TST7")
      (value "RX_Qp")
      (footprint "kp40x40")
      (description "Контактна  площадка")
      (fields (field (name "MANUFACTURER") "Конструктив"))
      (libsource (lib "Connectors") (part "KP"))
    )
    (comp (ref "TST8")
      (value "RX_Qn")
      (footprint "kp40x40")
      (description "Контактна  площадка")
      (fields (field (name "MANUFACTURER") "Конструктив"))
      (libsource (lib "Connectors") (part "KP"))
    )
    (comp (ref "U12")
      (value "LMS6002D")
      (footprint "DQFN120(9x9/0.5mm)")
      (description "Микросхема")
      (fields (field (name "MANUFACTURER") "Lime Microsystems"))
      (libsource (lib "Andy") (part "LMS6002D"))
    )
    (comp (ref "U14")
      (value "SPF-5043Z")
      (footprint "SOT-343[2X1.25]")
      (description "Микросхема")
      (fields (field (name "MANUFACTURER") "RFMD"))
      (libsource (lib "MicroCircuitsM-Z") (part "SPF-5043Z"))
    )
    (comp (ref "U29")
      (value "LD1117DT33")
      (footprint "Foot3-4pins:to-252")
      (description "Микросхема")
      (fields (field (name "MANUFACTURER") "STMicro"))
      (libsource (lib "altium-import") (part "root_0_LD1117FIX_"))
    )
    (comp (ref "U30")
      (value "LD1117S")
      (footprint "Foot3-4pins:SOT-223-1")
      (description "Микросхема")
      (fields (field (name "MANUFACTURER") "STMicro"))
      (libsource (lib "altium-import") (part "root_0_LD1117ADJ_"))
    )
    (comp (ref "U31")
      (value "LD1117S")
      (footprint "Foot3-4pins:SOT-223-1")
      (description "Микросхема")
      (fields (field (name "MANUFACTURER") "STMicro"))
      (libsource (lib "altium-import") (part "root_0_LD1117ADJ_"))
    )
    (comp (ref "U32")
      (value "LD1117S")
      (footprint "Foot3-4pins:SOT-223-1")
      (description "Микросхема")
      (fields (field (name "MANUFACTURER") "STMicro"))
      (libsource (lib "altium-import") (part "root_0_LD1117ADJ_"))
    )
    (comp (ref "Z1")
      (value "NFM3DPC223R1H3")
      (footprint "NFM3DP")
      (description "Фильтр")
      (fields (field (name "MANUFACTURER") "Murata"))
      (libsource (lib "altium-import") (part "root_0_NFM3DP_"))
    )
  )
  (nets
    (net (code "1") (name "+5V") (class "Default")
      (node (ref "C100") (pin "2") (pinfunction "2_2") (pintype "passive"))
      (node (ref "C67") (pin "2") (pinfunction "2_2") (pintype "passive"))
      (node (ref "L34") (pin "1") (pinfunction "1_1") (pintype "passive"))
    )
    (net (code "2") (name "+6V") (class "Default")
      (node (ref "C44") (pin "1") (pinfunction "1_1") (pintype "passive"))
      (node (ref "Z1") (pin "1") (pinfunction "1_1") (pintype "passive"))
    )
    (net (code "3") (name "/+1,8VALMS") (class "Default")
      (node (ref "C169") (pin "1") (pinfunction "+_1") (pintype "passive"))
      (node (ref "C72") (pin "1") (pinfunction "1_1") (pintype "passive"))
      (node (ref "L14") (pin "1") (pinfunction "1_1") (pintype "passive"))
      (node (ref "L15") (pin "1") (pinfunction "1_1") (pintype "passive"))
      (node (ref "R101") (pin "2") (pinfunction "2_2") (pintype "passive"))
      (node (ref "U32") (pin "2") (pinfunction "Vout_2") (pintype "passive"))
    )
    (net (code "4") (name "/+1,8VDLMS") (class "Default")
      (node (ref "C66") (pin "1") (pinfunction "+_1") (pintype "passive"))
      (node (ref "C71") (pin "1") (pinfunction "1_1") (pintype "passive"))
      (node (ref "L11") (pin "2") (pinfunction "2_2") (pintype "passive"))
      (node (ref "L16") (pin "2") (pinfunction "2_2") (pintype "passive"))
      (node (ref "L18") (pin "2") (pinfunction "2_2") (pintype "passive"))
      (node (ref "L19") (pin "2") (pinfunction "2_2") (pintype "passive"))
      (node (ref "L20") (pin "2") (pinfunction "2_2") (pintype "passive"))
      (node (ref "R100") (pin "2") (pinfunction "2_2") (pintype "passive"))
      (node (ref "U31") (pin "2") (pinfunction "Vout_2") (pintype "passive"))
    )
    (net (code "5") (name "/+2,5VLMS") (class "Default")
      (node (ref "C65") (pin "1") (pinfunction "+_1") (pintype "passive"))
      (node (ref "C68") (pin "1") (pinfunction "1_1") (pintype "passive"))
      (node (ref "C70") (pin "1") (pinfunction "1_1") (pintype "passive"))
      (node (ref "R103") (pin "1") (pinfunction "1_1") (pintype "passive"))
      (node (ref "R99") (pin "2") (pinfunction "2_2") (pintype "passive"))
      (node (ref "U12") (pin "66") (pinfunction "TXEN_66") (pintype "input"))
      (node (ref "U12") (pin "76") (pinfunction "RXEN_76") (pintype "input"))
      (node (ref "U30") (pin "2") (pinfunction "Vout_2") (pintype "passive"))
    )
    (net (code "6") (name "/+3,3VLMS") (class "Default")
      (node (ref "C64") (pin "1") (pinfunction "+_1") (pintype "passive"))
      (node (ref "C69") (pin "1") (pinfunction "1_1") (pintype "passive"))
      (node (ref "L12") (pin "1") (pinfunction "1_1") (pintype "passive"))
      (node (ref "L13") (pin "1") (pinfunction "1_1") (pintype "passive"))
      (node (ref "L17") (pin "1") (pinfunction "1_1") (pintype "passive"))
      (node (ref "L21") (pin "2") (pinfunction "2_2") (pintype "passive"))
      (node (ref "L22") (pin "1") (pinfunction "1_1") (pintype "passive"))
      (node (ref "L23") (pin "2") (pinfunction "2_2") (pintype "passive"))
      (node (ref "L24") (pin "1") (pinfunction "1_1") (pintype "passive"))
      (node (ref "L25") (pin "2") (pinfunction "2_2") (pintype "passive"))
      (node (ref "L26") (pin "1") (pinfunction "1_1") (pintype "passive"))
      (node (ref "L27") (pin "2") (pinfunction "2_2") (pintype "passive"))
      (node (ref "L28") (pin "1") (pinfunction "1_1") (pintype "passive"))
      (node (ref "L29") (pin "2") (pinfunction "2_2") (pintype "passive"))
      (node (ref "R95") (pin "2") (pinfunction "2_2") (pintype "passive"))
      (node (ref "U29") (pin "2") (pinfunction "Vout_2") (pintype "passive"))
    )
    (net (code "7") (name "/CLK_PLL") (class "Default")
      (node (ref "L6") (pin "1") (pinfunction "1_1") (pintype "passive"))
    )
    (net (code "8") (name "/CLK_TRX") (class "Default")
      (node (ref "R80") (pin "1") (pinfunction "1_1") (pintype "passive"))
    )
    (net (code "9") (name "/LMS_nRST") (class "Default")
      (node (ref "R95") (pin "1") (pinfunction "1_1") (pintype "passive"))
      (node (ref "U12") (pin "75") (pinfunction "~{RESET}_75") (pintype "input"))
    )
    (net (code "10") (name "/MISO") (class "Default")
      (node (ref "U12") (pin "68") (pinfunction "SDO_68") (pintype "output"))
    )
    (net (code "11") (name "/MOSI") (class "Default")
      (node (ref "U12") (pin "69") (pinfunction "SDIO_69") (pintype "bidirectional"))
    )
    (net (code "12") (name "/RX") (class "Default")
      (node (ref "C111") (pin "1") (pinfunction "1_1") (pintype "passive"))
      (node (ref "ESD4") (pin "2") (pinfunction "A2_2") (pintype "passive"))
    )
    (net (code "13") (name "/RXD0") (class "Default")
      (node (ref "U12") (pin "15") (pinfunction "RXD0_15") (pintype "output"))
    )
    (net (code "14") (name "/RXD1") (class "Default")
      (node (ref "U12") (pin "14") (pinfunction "RXD1_14") (pintype "output"))
    )
    (net (code "15") (name "/RXD2") (class "Default")
      (node (ref "U12") (pin "13") (pinfunction "RXD2_13") (pintype "output"))
    )
    (net (code "16") (name "/RXD3") (class "Default")
      (node (ref "U12") (pin "10") (pinfunction "RXD3_10") (pintype "output"))
    )
    (net (code "17") (name "/RXD4") (class "Default")
      (node (ref "U12") (pin "11") (pinfunction "RXD4_11") (pintype "output"))
    )
    (net (code "18") (name "/RXD5") (class "Default")
      (node (ref "U12") (pin "8") (pinfunction "RXD5_8") (pintype "output"))
    )
    (net (code "19") (name "/RXD6") (class "Default")
      (node (ref "U12") (pin "9") (pinfunction "RXD6_9") (pintype "output"))
    )
    (net (code "20") (name "/RXD7") (class "Default")
      (node (ref "U12") (pin "6") (pinfunction "RXD7_6") (pintype "output"))
    )
    (net (code "21") (name "/RXD8") (class "Default")
      (node (ref "U12") (pin "5") (pinfunction "RXD8_5") (pintype "output"))
    )
    (net (code "22") (name "/RXD9") (class "Default")
      (node (ref "U12") (pin "4") (pinfunction "RXD9_4") (pintype "output"))
    )
    (net (code "23") (name "/RXD10") (class "Default")
      (node (ref "U12") (pin "3") (pinfunction "RXD10_3") (pintype "output"))
    )
    (net (code "24") (name "/RXD11") (class "Default")
      (node (ref "U12") (pin "2") (pinfunction "RXD11_2") (pintype "output"))
    )
    (net (code "25") (name "/RXIQSEL") (class "Default")
      (node (ref "U12") (pin "16") (pinfunction "RXIQSEL_16") (pintype "output"))
    )
    (net (code "26") (name "/SCLK") (class "Default")
      (node (ref "U12") (pin "70") (pinfunction "SCLK_70") (pintype "input"))
    )
    (net (code "27") (name "/SCN") (class "Default")
      (node (ref "C112") (pin "2") (pinfunction "2_2") (pintype "passive"))
      (node (ref "ESD5") (pin "2") (pinfunction "A2_2") (pintype "passive"))
    )
    (net (code "28") (name "/SEN") (class "Default")
      (node (ref "U12") (pin "67") (pinfunction "SEN_67") (pintype "input"))
    )
    (net (code "29") (name "/TX") (class "Default")
      (node (ref "C109") (pin "2") (pinfunction "2_2") (pintype "passive"))
      (node (ref "C110") (pin "2") (pinfunction "2_2") (pintype "passive"))
      (node (ref "ESD3") (pin "2") (pinfunction "A2_2") (pintype "passive"))
    )
    (net (code "30") (name "/TXD0") (class "Default")
      (node (ref "U12") (pin "21") (pinfunction "TXD0_21") (pintype "input"))
    )
    (net (code "31") (name "/TXD1") (class "Default")
      (node (ref "U12") (pin "22") (pinfunction "TXD1_22") (pintype "input"))
    )
    (net (code "32") (name "/TXD2") (class "Default")
      (node (ref "U12") (pin "23") (pinfunction "TXD2_23") (pintype "input"))
    )
    (net (code "33") (name "/TXD3") (class "Default")
      (node (ref "U12") (pin "24") (pinfunction "TXD3_24") (pintype "input"))
    )
    (net (code "34") (name "/TXD4") (class "Default")
      (node (ref "U12") (pin "25") (pinfunction "TXD4_25") (pintype "input"))
    )
    (net (code "35") (name "/TXD5") (class "Default")
      (node (ref "U12") (pin "26") (pinfunction "TXD5_26") (pintype "input"))
    )
    (net (code "36") (name "/TXD6") (class "Default")
      (node (ref "U12") (pin "27") (pinfunction "TXD6_27") (pintype "input"))
    )
    (net (code "37") (name "/TXD7") (class "Default")
      (node (ref "U12") (pin "28") (pinfunction "TXD7_28") (pintype "input"))
    )
    (net (code "38") (name "/TXD8") (class "Default")
      (node (ref "U12") (pin "29") (pinfunction "TXD8_29") (pintype "input"))
    )
    (net (code "39") (name "/TXD9") (class "Default")
      (node (ref "U12") (pin "30") (pinfunction "TXD9_30") (pintype "input"))
    )
    (net (code "40") (name "/TXD10") (class "Default")
      (node (ref "U12") (pin "31") (pinfunction "TXD10_31") (pintype "input"))
    )
    (net (code "41") (name "/TXD11") (class "Default")
      (node (ref "U12") (pin "32") (pinfunction "TXD11_32") (pintype "input"))
    )
    (net (code "42") (name "/TXIQSEL") (class "Default")
      (node (ref "U12") (pin "20") (pinfunction "TXIQSEL_20") (pintype "input"))
    )
    (net (code "43") (name "GND") (class "Default")
      (node (ref "C100") (pin "1") (pinfunction "1_1") (pintype "passive"))
      (node (ref "C169") (pin "2") (pinfunction "-_2") (pintype "passive"))
      (node (ref "C44") (pin "2") (pinfunction "2_2") (pintype "passive"))
      (node (ref "C45") (pin "1") (pinfunction "1_1") (pintype "passive"))
      (node (ref "C46") (pin "2") (pinfunction "2_2") (pintype "passive"))
      (node (ref "C47") (pin "2") (pinfunction "2_2") (pintype "passive"))
      (node (ref "C48") (pin "2") (pinfunction "2_2") (pintype "passive"))
      (node (ref "C49") (pin "2") (pinfunction "2_2") (pintype "passive"))
      (node (ref "C50") (pin "2") (pinfunction "2_2") (pintype "passive"))
      (node (ref "C51") (pin "2") (pinfunction "-_2") (pintype "passive"))
      (node (ref "C52") (pin "2") (pinfunction "-_2") (pintype "passive"))
      (node (ref "C53") (pin "2") (pinfunction "-_2") (pintype "passive"))
      (node (ref "C54") (pin "2") (pinfunction "-_2") (pintype "passive"))
      (node (ref "C55") (pin "2") (pinfunction "2_2") (pintype "passive"))
      (node (ref "C56") (pin "2") (pinfunction "2_2") (pintype "passive"))
      (node (ref "C57") (pin "2") (pinfunction "2_2") (pintype "passive"))
      (node (ref "C58") (pin "2") (pinfunction "2_2") (pintype "passive"))
      (node (ref "C59") (pin "1") (pinfunction "1_1") (pintype "passive"))
      (node (ref "C60") (pin "1") (pinfunction "1_1") (pintype "passive"))
      (node (ref "C61") (pin "1") (pinfunction "1_1") (pintype "passive"))
      (node (ref "C62") (pin "1") (pinfunction "1_1") (pintype "passive"))
      (node (ref "C63") (pin "1") (pinfunction "1_1") (pintype "passive"))
      (node (ref "C64") (pin "2") (pinfunction "-_2") (pintype "passive"))
      (node (ref "C65") (pin "2") (pinfunction "-_2") (pintype "passive"))
      (node (ref "C66") (pin "2") (pinfunction "-_2") (pintype "passive"))
      (node (ref "C67") (pin "1") (pinfunction "1_1") (pintype "passive"))
      (node (ref "C68") (pin "2") (pinfunction "2_2") (pintype "passive"))
      (node (ref "C69") (pin "2") (pinfunction "2_2") (pintype "passive"))
      (node (ref "C70") (pin "2") (pinfunction "2_2") (pintype "passive"))
      (node (ref "C71") (pin "2") (pinfunction "2_2") (pintype "passive"))
      (node (ref "C72") (pin "2") (pinfunction "2_2") (pintype "passive"))
      (node (ref "C73") (pin "2") (pinfunction "2_2") (pintype "passive"))
      (node (ref "C74") (pin "2") (pinfunction "2_2") (pintype "passive"))
      (node (ref "C75") (pin "2") (pinfunction "2_2") (pintype "passive"))
      (node (ref "C76") (pin "2") (pinfunction "2_2") (pintype "passive"))
      (node (ref "C77") (pin "2") (pinfunction "2_2") (pintype "passive"))
      (node (ref "C78") (pin "2") (pinfunction "2_2") (pintype "passive"))
      (node (ref "C79") (pin "2") (pinfunction "2_2") (pintype "passive"))
      (node (ref "C80") (pin "2") (pinfunction "2_2") (pintype "passive"))
      (node (ref "C81") (pin "2") (pinfunction "2_2") (pintype "passive"))
      (node (ref "C82") (pin "2") (pinfunction "2_2") (pintype "passive"))
      (node (ref "C84") (pin "1") (pinfunction "1_1") (pintype "passive"))
      (node (ref "C85") (pin "1") (pinfunction "1_1") (pintype "passive"))
      (node (ref "C86") (pin "2") (pinfunction "2_2") (pintype "passive"))
      (node (ref "C87") (pin "2") (pinfunction "2_2") (pintype "passive"))
      (node (ref "C88") (pin "2") (pinfunction "2_2") (pintype "passive"))
      (node (ref "C89") (pin "2") (pinfunction "2_2") (pintype "passive"))
      (node (ref "C90") (pin "2") (pinfunction "2_2") (pintype "passive"))
      (node (ref "C91") (pin "2") (pinfunction "2_2") (pintype "passive"))
      (node (ref "C92") (pin "2") (pinfunction "2_2") (pintype "passive"))
      (node (ref "C93") (pin "2") (pinfunction "2_2") (pintype "passive"))
      (node (ref "C94") (pin "1") (pinfunction "1_1") (pintype "passive"))
      (node (ref "C95") (pin "2") (pinfunction "2_2") (pintype "passive"))
      (node (ref "C97") (pin "1") (pinfunction "1_1") (pintype "passive"))
      (node (ref "C98") (pin "2") (pinfunction "2_2") (pintype "passive"))
      (node (ref "ESD3") (pin "1") (pinfunction "A1_1") (pintype "passive"))
      (node (ref "ESD4") (pin "1") (pinfunction "A1_1") (pintype "passive"))
      (node (ref "ESD5") (pin "1") (pinfunction "A1_1") (pintype "passive"))
      (node (ref "R106") (pin "1") (pinfunction "1_1") (pintype "passive"))
      (node (ref "R107") (pin "1") (pinfunction "1_1") (pintype "passive"))
      (node (ref "R108") (pin "1") (pinfunction "1_1") (pintype "passive"))
      (node (ref "R110") (pin "1") (pinfunction "1_1") (pintype "passive"))
      (node (ref "R111") (pin "1") (pinfunction "1_1") (pintype "passive"))
      (node (ref "R112") (pin "1") (pinfunction "1_1") (pintype "passive"))
      (node (ref "R113") (pin "1") (pinfunction "1_1") (pintype "passive"))
      (node (ref "R121") (pin "2") (pinfunction "2_2") (pintype "passive"))
      (node (ref "R96") (pin "1") (pinfunction "1_1") (pintype "passive"))
      (node (ref "R97") (pin "1") (pinfunction "1_1") (pintype "passive"))
      (node (ref "R98") (pin "1") (pinfunction "1_1") (pintype "passive"))
      (node (ref "T1") (pin "6") (pinfunction "Pri_Dot_6") (pintype "passive"))
      (node (ref "T2") (pin "4") (pinfunction "Pri_4") (pintype "passive"))
      (node (ref "T3") (pin "2") (pinfunction "Sec_CT_2") (pintype "passive"))
      (node (ref "T3") (pin "6") (pinfunction "Pri_Dot_6") (pintype "passive"))
      (node (ref "U12") (pin "0") (pinfunction "GND_0") (pintype "power_in"))
      (node (ref "U12") (pin "53") (pinfunction "UNUSED_53") (pintype "passive"))
      (node (ref "U12") (pin "55") (pinfunction "UNUSED_55") (pintype "passive"))
      (node (ref "U12") (pin "88") (pinfunction "UNUSED_88") (pintype "passive"))
      (node (ref "U12") (pin "93") (pinfunction "UNUSED_93") (pintype "passive"))
      (node (ref "U12") (pin "97") (pinfunction "RXIN1EP_97") (pintype "bidirectional"))
      (node (ref "U12") (pin "99") (pinfunction "RXIN1EN_99") (pintype "bidirectional"))
      (node (ref "U14") (pin "2") (pinfunction "GND_2") (pintype "power_in"))
      (node (ref "U14") (pin "4") (pinfunction "GND_4") (pintype "power_in"))
      (node (ref "U29") (pin "1") (pinfunction "GND_1") (pintype "passive"))
      (node (ref "Z1") (pin "2") (pinfunction "2_2") (pintype "passive"))
    )
    (net (code "44") (name "Net-(C46-Pad1)") (class "Default")
      (node (ref "C46") (pin "1") (pinfunction "1_1") (pintype "passive"))
      (node (ref "C47") (pin "1") (pinfunction "1_1") (pintype "passive"))
      (node (ref "C48") (pin "1") (pinfunction "1_1") (pintype "passive"))
      (node (ref "C49") (pin "1") (pinfunction "1_1") (pintype "passive"))
      (node (ref "C50") (pin "1") (pinfunction "1_1") (pintype "passive"))
      (node (ref "L10") (pin "1") (pinfunction "1_1") (pintype "passive"))
      (node (ref "L7") (pin "1") (pinfunction "1_1") (pintype "passive"))
      (node (ref "L8") (pin "1") (pinfunction "1_1") (pintype "passive"))
      (node (ref "L9") (pin "1") (pinfunction "1_1") (pintype "passive"))
      (node (ref "Z1") (pin "3") (pinfunction "3_3") (pintype "passive"))
    )
    (net (code "45") (name "Net-(C51-+)") (class "Default")
      (node (ref "C51") (pin "1") (pinfunction "+_1") (pintype "passive"))
      (node (ref "C55") (pin "1") (pinfunction "1_1") (pintype "passive"))
      (node (ref "L7") (pin "2") (pinfunction "2_2") (pintype "passive"))
      (node (ref "U29") (pin "3") (pinfunction "Vin_3") (pintype "passive"))
    )
    (net (code "46") (name "Net-(C52-+)") (class "Default")
      (node (ref "C52") (pin "1") (pinfunction "+_1") (pintype "passive"))
      (node (ref "C56") (pin "1") (pinfunction "1_1") (pintype "passive"))
      (node (ref "L8") (pin "2") (pinfunction "2_2") (pintype "passive"))
      (node (ref "U30") (pin "3") (pinfunction "Vin_3") (pintype "passive"))
    )
    (net (code "47") (name "Net-(C53-+)") (class "Default")
      (node (ref "C53") (pin "1") (pinfunction "+_1") (pintype "passive"))
      (node (ref "C57") (pin "1") (pinfunction "1_1") (pintype "passive"))
      (node (ref "L9") (pin "2") (pinfunction "2_2") (pintype "passive"))
      (node (ref "U31") (pin "3") (pinfunction "Vin_3") (pintype "passive"))
    )
    (net (code "48") (name "Net-(C54-+)") (class "Default")
      (node (ref "C54") (pin "1") (pinfunction "+_1") (pintype "passive"))
      (node (ref "C58") (pin "1") (pinfunction "1_1") (pintype "passive"))
      (node (ref "L10") (pin "2") (pinfunction "2_2") (pintype "passive"))
      (node (ref "U32") (pin "3") (pinfunction "Vin_3") (pintype "passive"))
    )
    (net (code "49") (name "Net-(C60-Pad2)") (class "Default")
      (node (ref "C60") (pin "2") (pinfunction "2_2") (pintype "passive"))
      (node (ref "L18") (pin "1") (pinfunction "1_1") (pintype "passive"))
      (node (ref "R104") (pin "1") (pinfunction "1_1") (pintype "passive"))
      (node (ref "R105") (pin "1") (pinfunction "1_1") (pintype "passive"))
    )
    (net (code "50") (name "Net-(C83-Pad2)") (class "Default")
      (node (ref "C83") (pin "2") (pinfunction "2_2") (pintype "passive"))
      (node (ref "R106") (pin "2") (pinfunction "2_2") (pintype "passive"))
    )
    (net (code "51") (name "Net-(C94-Pad2)") (class "Default")
      (node (ref "C94") (pin "2") (pinfunction "2_2") (pintype "passive"))
      (node (ref "C95") (pin "1") (pinfunction "1_1") (pintype "passive"))
      (node (ref "L29") (pin "1") (pinfunction "1_1") (pintype "passive"))
      (node (ref "L30") (pin "1") (pinfunction "1_1") (pintype "passive"))
      (node (ref "L31") (pin "1") (pinfunction "1_1") (pintype "passive"))
    )
    (net (code "52") (name "Net-(C99-Pad2)") (class "Default")
      (node (ref "C99") (pin "2") (pinfunction "2_2") (pintype "passive"))
      (node (ref "R121") (pin "1") (pinfunction "1_1") (pintype "passive"))
    )
    (net (code "53") (name "Net-(C102-Pad2)") (class "Default")
      (node (ref "C102") (pin "2") (pinfunction "2_2") (pintype "passive"))
      (node (ref "L32") (pin "1") (pinfunction "1_1") (pintype "passive"))
    )
    (net (code "54") (name "Net-(C103-Pad2)") (class "Default")
      (node (ref "C103") (pin "2") (pinfunction "2_2") (pintype "passive"))
      (node (ref "L33") (pin "1") (pinfunction "1_1") (pintype "passive"))
    )
    (net (code "55") (name "Net-(C108-Pad2)") (class "Default")
      (node (ref "C108") (pin "2") (pinfunction "2_2") (pintype "passive"))
      (node (ref "C109") (pin "1") (pinfunction "1_1") (pintype "passive"))
    )
    (net (code "56") (name "Net-(C146-Pad1)") (class "Default")
      (node (ref "C146") (pin "1") (pinfunction "1_1") (pintype "passive"))
      (node (ref "C45") (pin "2") (pinfunction "2_2") (pintype "passive"))
      (node (ref "L6") (pin "2") (pinfunction "2_2") (pintype "passive"))
    )
    (net (code "57") (name "Net-(R107-Pad2)") (class "Default")
      (node (ref "R107") (pin "2") (pinfunction "2_2") (pintype "passive"))
      (node (ref "R114") (pin "1") (pinfunction "1_1") (pintype "passive"))
    )
    (net (code "58") (name "Net-(T1-Pri)") (class "Default")
      (node (ref "C101") (pin "1") (pinfunction "1_1") (pintype "passive"))
      (node (ref "C108") (pin "1") (pinfunction "1_1") (pintype "passive"))
      (node (ref "T1") (pin "4") (pinfunction "Pri_4") (pintype "passive"))
    )
    (net (code "59") (name "Net-(T1-Sec)") (class "Default")
      (node (ref "C105") (pin "2") (pinfunction "2_2") (pintype "passive"))
      (node (ref "T1") (pin "1") (pinfunction "Sec_1") (pintype "passive"))
    )
    (net (code "60") (name "Net-(T1-Sec_Dot)") (class "Default")
      (node (ref "C104") (pin "2") (pinfunction "2_2") (pintype "passive"))
      (node (ref "T1") (pin "3") (pinfunction "Sec_Dot_3") (pintype "passive"))
    )
    (net (code "61") (name "Net-(T2-Pri_Dot)") (class "Default")
      (node (ref "C111") (pin "2") (pinfunction "2_2") (pintype "passive"))
      (node (ref "T2") (pin "6") (pinfunction "Pri_Dot_6") (pintype "passive"))
    )
    (net (code "62") (name "Net-(T2-Sec)") (class "Default")
      (node (ref "C106") (pin "2") (pinfunction "2_2") (pintype "passive"))
      (node (ref "T2") (pin "1") (pinfunction "Sec_1") (pintype "passive"))
    )
    (net (code "63") (name "Net-(T2-Sec_Dot)") (class "Default")
      (node (ref "C107") (pin "2") (pinfunction "2_2") (pintype "passive"))
      (node (ref "T2") (pin "3") (pinfunction "Sec_Dot_3") (pintype "passive"))
    )
    (net (code "64") (name "Net-(T3-Pri)") (class "Default")
      (node (ref "C112") (pin "1") (pinfunction "1_1") (pintype "passive"))
      (node (ref "T3") (pin "4") (pinfunction "Pri_4") (pintype "passive"))
    )
    (net (code "65") (name "Net-(T3-Sec)") (class "Default")
      (node (ref "L32") (pin "2") (pinfunction "2_2") (pintype "passive"))
      (node (ref "T3") (pin "1") (pinfunction "Sec_1") (pintype "passive"))
    )
    (net (code "66") (name "Net-(T3-Sec_Dot)") (class "Default")
      (node (ref "L33") (pin "2") (pinfunction "2_2") (pintype "passive"))
      (node (ref "T3") (pin "3") (pinfunction "Sec_Dot_3") (pintype "passive"))
    )
    (net (code "67") (name "Net-(U12A-PVDDAD33A)") (class "Default")
      (node (ref "C81") (pin "1") (pinfunction "1_1") (pintype "passive"))
      (node (ref "U12") (pin "1") (pinfunction "PVDDAD33A_1") (pintype "power_in"))
    )
    (net (code "68") (name "Net-(U12A-PVDDAD33D)") (class "Default")
      (node (ref "C77") (pin "1") (pinfunction "1_1") (pintype "passive"))
      (node (ref "R103") (pin "2") (pinfunction "2_2") (pintype "passive"))
      (node (ref "U12") (pin "34") (pinfunction "PVDDAD33D_34") (pintype "power_in"))
    )
    (net (code "69") (name "Net-(U12A-PVDDSPI33)") (class "Default")
      (node (ref "C80") (pin "1") (pinfunction "1_1") (pintype "passive"))
      (node (ref "L13") (pin "2") (pinfunction "2_2") (pintype "passive"))
      (node (ref "U12") (pin "74") (pinfunction "PVDDSPI33_74") (pintype "power_in"))
    )
    (net (code "70") (name "Net-(U12A-PVDDVGG)") (class "Default")
      (node (ref "C76") (pin "1") (pinfunction "1_1") (pintype "passive"))
      (node (ref "L17") (pin "2") (pinfunction "2_2") (pintype "passive"))
      (node (ref "U12") (pin "7") (pinfunction "PVDDVGG_7") (pintype "power_in"))
    )
    (net (code "71") (name "Net-(U12A-RAVDD18)") (class "Default")
      (node (ref "C62") (pin "2") (pinfunction "2_2") (pintype "passive"))
      (node (ref "L11") (pin "1") (pinfunction "1_1") (pintype "passive"))
      (node (ref "U12") (pin "35") (pinfunction "RAVDD18_35") (pintype "power_in"))
    )
    (net (code "72") (name "Net-(U12A-RDVDD18)") (class "Default")
      (node (ref "C63") (pin "2") (pinfunction "2_2") (pintype "passive"))
      (node (ref "L20") (pin "1") (pinfunction "1_1") (pintype "passive"))
      (node (ref "U12") (pin "33") (pinfunction "RDVDD18_33") (pintype "power_in"))
      (node (ref "U12") (pin "36") (pinfunction "TDVDD18_36") (pintype "power_in"))
    )
    (net (code "73") (name "Net-(U12A-RXPVDD33)") (class "Default")
      (node (ref "C88") (pin "1") (pinfunction "1_1") (pintype "passive"))
      (node (ref "L23") (pin "1") (pinfunction "1_1") (pintype "passive"))
      (node (ref "U12") (pin "107") (pinfunction "RXPVDD33_107") (pintype "power_in"))
      (node (ref "U12") (pin "109") (pinfunction "RXVCCTIA33_109") (pintype "power_in"))
    )
    (net (code "74") (name "Net-(U12A-RXPVDDPLL33A)") (class "Default")
      (node (ref "C93") (pin "1") (pinfunction "1_1") (pintype "passive"))
      (node (ref "L28") (pin "2") (pinfunction "2_2") (pintype "passive"))
      (node (ref "U12") (pin "86") (pinfunction "RXPVDDPLL33A_86") (pintype "power_in"))
    )
    (net (code "75") (name "Net-(U12A-RXPVDDPLL33B)") (class "Default")
      (node (ref "C91") (pin "1") (pinfunction "1_1") (pintype "passive"))
      (node (ref "L26") (pin "2") (pinfunction "2_2") (pintype "passive"))
      (node (ref "U12") (pin "78") (pinfunction "RXVCCCHP33_78") (pintype "power_in"))
      (node (ref "U12") (pin "79") (pinfunction "RXVCCLOB33_79") (pintype "power_in"))
      (node (ref "U12") (pin "81") (pinfunction "RXPVDDPLL33B_81") (pintype "power_in"))
      (node (ref "U12") (pin "82") (pinfunction "RXVCCVCO33_82") (pintype "power_in"))
      (node (ref "U12") (pin "85") (pinfunction "RXVCCPLL33_85") (pintype "power_in"))
    )
    (net (code "76") (name "Net-(U12A-RXVCCLNA33)") (class "Default")
      (node (ref "C90") (pin "1") (pinfunction "1_1") (pintype "passive"))
      (node (ref "L25") (pin "1") (pinfunction "1_1") (pintype "passive"))
      (node (ref "U12") (pin "101") (pinfunction "RXVCCLNA33_101") (pintype "power_in"))
      (node (ref "U12") (pin "90") (pinfunction "RXVCCMIX33_90") (pintype "power_in"))
    )
    (net (code "77") (name "Net-(U12A-RXVCCLPF33)") (class "Default")
      (node (ref "C86") (pin "1") (pinfunction "1_1") (pintype "passive"))
      (node (ref "L21") (pin "1") (pinfunction "1_1") (pintype "passive"))
      (node (ref "U12") (pin "111") (pinfunction "RXVCCLPF33_111") (pintype "power_in"))
      (node (ref "U12") (pin "112") (pinfunction "RXVCCVGA33_112") (pintype "power_in"))
    )
    (net (code "78") (name "Net-(U12A-RXVCCPLL18)") (class "Default")
      (node (ref "C61") (pin "2") (pinfunction "2_2") (pintype "passive"))
      (node (ref "L16") (pin "1") (pinfunction "1_1") (pintype "passive"))
      (node (ref "U12") (pin "83") (pinfunction "RXVCCPLL18_83") (pintype "power_in"))
    )
    (net (code "79") (name "Net-(U12A-RXVDDVCO18)") (class "Default")
      (node (ref "C75") (pin "1") (pinfunction "1_1") (pintype "passive"))
      (node (ref "C79") (pin "1") (pinfunction "1_1") (pintype "passive"))
      (node (ref "L15") (pin "2") (pinfunction "2_2") (pintype "passive"))
      (node (ref "U12") (pin "84") (pinfunction "RXVDDVCO18_84") (pintype "power_in"))
    )
    (net (code "80") (name "Net-(U12A-TAVDD33)") (class "Default")
      (node (ref "C74") (pin "1") (pinfunction "1_1") (pintype "passive"))
      (node (ref "L12") (pin "2") (pinfunction "2_2") (pintype "passive"))
      (node (ref "U12") (pin "37") (pinfunction "TAVDD33_37") (pintype "power_in"))
    )
    (net (code "81") (name "Net-(U12A-TRXVDDDSM18)") (class "Default")
      (node (ref "R104") (pin "2") (pinfunction "2_2") (pintype "passive"))
      (node (ref "U12") (pin "72") (pinfunction "TRXVDDDSM18_72") (pintype "power_in"))
    )
    (net (code "82") (name "Net-(U12A-TXPVDD33)") (class "Default")
      (node (ref "C92") (pin "1") (pinfunction "1_1") (pintype "passive"))
      (node (ref "L27") (pin "1") (pinfunction "1_1") (pintype "passive"))
      (node (ref "U12") (pin "43") (pinfunction "TXVCCLPF33_43") (pintype "power_in"))
      (node (ref "U12") (pin "45") (pinfunction "TXVCCMIX33_45") (pintype "power_in"))
      (node (ref "U12") (pin "47") (pinfunction "TXPVDD33_47") (pintype "power_in"))
      (node (ref "U12") (pin "49") (pinfunction "TXVCCDRV33_49") (pintype "power_in"))
    )
    (net (code "83") (name "Net-(U12A-TXPVDDPLL33A)") (class "Default")
      (node (ref "C87") (pin "1") (pinfunction "1_1") (pintype "passive"))
      (node (ref "L22") (pin "2") (pinfunction "2_2") (pintype "passive"))
      (node (ref "U12") (pin "58") (pinfunction "TXPVDDPLL33A_58") (pintype "power_in"))
    )
    (net (code "84") (name "Net-(U12A-TXPVDDPLL33B)") (class "Default")
      (node (ref "C89") (pin "1") (pinfunction "1_1") (pintype "passive"))
      (node (ref "L24") (pin "2") (pinfunction "2_2") (pintype "passive"))
      (node (ref "U12") (pin "59") (pinfunction "TXVCCVCO33_59") (pintype "power_in"))
      (node (ref "U12") (pin "62") (pinfunction "TXPVDDPLL33B_62") (pintype "power_in"))
      (node (ref "U12") (pin "63") (pinfunction "TXVCCHP33_63") (pintype "power_in"))
    )
    (net (code "85") (name "Net-(U12A-TXVCCPLL18)") (class "Default")
      (node (ref "C59") (pin "2") (pinfunction "2_2") (pintype "passive"))
      (node (ref "L19") (pin "1") (pinfunction "1_1") (pintype "passive"))
      (node (ref "U12") (pin "61") (pinfunction "TXVCCPLL18_61") (pintype "power_in"))
    )
    (net (code "86") (name "Net-(U12A-TXVDDVCO18)") (class "Default")
      (node (ref "C73") (pin "1") (pinfunction "1_1") (pintype "passive"))
      (node (ref "C78") (pin "1") (pinfunction "1_1") (pintype "passive"))
      (node (ref "L14") (pin "2") (pinfunction "2_2") (pintype "passive"))
      (node (ref "U12") (pin "60") (pinfunction "TXVDDVCO18_60") (pintype "power_in"))
    )
    (net (code "87") (name "Net-(U12A-VSPI18)") (class "Default")
      (node (ref "R105") (pin "2") (pinfunction "2_2") (pintype "passive"))
      (node (ref "U12") (pin "73") (pinfunction "VSPI18_73") (pintype "power_in"))
    )
    (net (code "88") (name "Net-(U12B-PLLCLK)") (class "Default")
      (node (ref "C146") (pin "2") (pinfunction "2_2") (pintype "passive"))
      (node (ref "U12") (pin "71") (pinfunction "PLLCLK_71") (pintype "input"))
    )
    (net (code "89") (name "Net-(U12B-PLLCLK_OUT)") (class "Default")
      (node (ref "TST3") (pin "1") (pinfunction "1_1") (pintype "passive"))
      (node (ref "U12") (pin "41") (pinfunction "PLLCLK_OUT_41") (pintype "output"))
    )
    (net (code "90") (name "Net-(U12B-RXCLK)") (class "Default")
      (node (ref "R80") (pin "2") (pinfunction "2_2") (pintype "passive"))
      (node (ref "U12") (pin "17") (pinfunction "RXCLK_17") (pintype "input"))
      (node (ref "U12") (pin "19") (pinfunction "TXCLK_19") (pintype "input"))
    )
    (net (code "91") (name "Net-(U12B-TSTD_OUT1)") (class "Default")
      (node (ref "TST1") (pin "1") (pinfunction "1_1") (pintype "passive"))
      (node (ref "U12") (pin "65") (pinfunction "TSTD_OUT1_65") (pintype "output"))
    )
    (net (code "92") (name "Net-(U12B-TSTD_OUT2)") (class "Default")
      (node (ref "TST2") (pin "1") (pinfunction "1_1") (pintype "passive"))
      (node (ref "U12") (pin "77") (pinfunction "TSTD_OUT2_77") (pintype "output"))
    )
    (net (code "93") (name "Net-(U12C-AUXIN{slash}ATPOUT)") (class "Default")
      (node (ref "TST4") (pin "1") (pinfunction "1_1") (pintype "passive"))
      (node (ref "U12") (pin "42") (pinfunction "AUXIN/ATPOUT_42") (pintype "bidirectional"))
    )
    (net (code "94") (name "Net-(U12C-RXCPOUT)") (class "Default")
      (node (ref "C98") (pin "1") (pinfunction "1_1") (pintype "passive"))
      (node (ref "C99") (pin "1") (pinfunction "1_1") (pintype "passive"))
      (node (ref "R119") (pin "2") (pinfunction "2_2") (pintype "passive"))
      (node (ref "U12") (pin "80") (pinfunction "RXCPOUT_80") (pintype "output"))
    )
    (net (code "95") (name "Net-(U12C-RXOUTIN)") (class "Default")
      (node (ref "TST6") (pin "1") (pinfunction "1_1") (pintype "passive"))
      (node (ref "U12") (pin "115") (pinfunction "RXOUTIN_115") (pintype "output"))
    )
    (net (code "96") (name "Net-(U12C-RXOUTIP)") (class "Default")
      (node (ref "TST5") (pin "1") (pinfunction "1_1") (pintype "passive"))
      (node (ref "U12") (pin "116") (pinfunction "RXOUTIP_116") (pintype "output"))
    )
    (net (code "97") (name "Net-(U12C-RXOUTQN)") (class "Default")
      (node (ref "TST8") (pin "1") (pinfunction "1_1") (pintype "passive"))
      (node (ref "U12") (pin "114") (pinfunction "RXOUTQN_114") (pintype "output"))
    )
    (net (code "98") (name "Net-(U12C-RXOUTQP)") (class "Default")
      (node (ref "TST7") (pin "1") (pinfunction "1_1") (pintype "passive"))
      (node (ref "U12") (pin "113") (pinfunction "RXOUTQP_113") (pintype "output"))
    )
    (net (code "99") (name "Net-(U12C-RXVTUNE)") (class "Default")
      (node (ref "C97") (pin "2") (pinfunction "2_2") (pintype "passive"))
      (node (ref "R119") (pin "1") (pinfunction "1_1") (pintype "passive"))
      (node (ref "U12") (pin "87") (pinfunction "RXVTUNE_87") (pintype "input"))
    )
    (net (code "100") (name "Net-(U12C-TXCPOUT)") (class "Default")
      (node (ref "C82") (pin "1") (pinfunction "1_1") (pintype "passive"))
      (node (ref "C83") (pin "1") (pinfunction "1_1") (pintype "passive"))
      (node (ref "R109") (pin "1") (pinfunction "1_1") (pintype "passive"))
      (node (ref "U12") (pin "64") (pinfunction "TXCPOUT_64") (pintype "output"))
    )
    (net (code "101") (name "Net-(U12C-TXININ)") (class "Default")
      (node (ref "R111") (pin "2") (pinfunction "2_2") (pintype "passive"))
      (node (ref "U12") (pin "51") (pinfunction "TXININ_51") (pintype "input"))
    )
    (net (code "102") (name "Net-(U12C-TXINIP)") (class "Default")
      (node (ref "R110") (pin "2") (pinfunction "2_2") (pintype "passive"))
      (node (ref "U12") (pin "52") (pinfunction "TXINIP_52") (pintype "input"))
    )
    (net (code "103") (name "Net-(U12C-TXINQN)") (class "Default")
      (node (ref "R113") (pin "2") (pinfunction "2_2") (pintype "passive"))
      (node (ref "U12") (pin "56") (pinfunction "TXINQN_56") (pintype "input"))
    )
    (net (code "104") (name "Net-(U12C-TXINQP)") (class "Default")
      (node (ref "R112") (pin "2") (pinfunction "2_2") (pintype "passive"))
      (node (ref "U12") (pin "54") (pinfunction "TXINQP_54") (pintype "input"))
    )
    (net (code "105") (name "Net-(U12C-TXVTUNE)") (class "Default")
      (node (ref "C84") (pin "2") (pinfunction "2_2") (pintype "passive"))
      (node (ref "R109") (pin "2") (pinfunction "2_2") (pintype "passive"))
      (node (ref "U12") (pin "57") (pinfunction "TXVTUNE_57") (pintype "input"))
    )
    (net (code "106") (name "Net-(U12C-VREFAD)") (class "Default")
      (node (ref "C85") (pin "2") (pinfunction "2_2") (pintype "passive"))
      (node (ref "U12") (pin "38") (pinfunction "VREFAD_38") (pintype "bidirectional"))
    )
    (net (code "107") (name "Net-(U12C-XRES12k)") (class "Default")
      (node (ref "R108") (pin "2") (pinfunction "2_2") (pintype "passive"))
      (node (ref "U12") (pin "89") (pinfunction "XRES12k_89") (pintype "bidirectional"))
    )
    (net (code "108") (name "Net-(U12C-XRESAD)") (class "Default")
      (node (ref "R114") (pin "2") (pinfunction "2_2") (pintype "passive"))
      (node (ref "U12") (pin "39") (pinfunction "XRESAD_39") (pintype "bidirectional"))
    )
    (net (code "109") (name "Net-(U12D-RXIN1N)") (class "Default")
      (node (ref "C107") (pin "1") (pinfunction "1_1") (pintype "passive"))
      (node (ref "U12") (pin "98") (pinfunction "RXIN1N_98") (pintype "input"))
    )
    (net (code "110") (name "Net-(U12D-RXIN1P)") (class "Default")
      (node (ref "C106") (pin "1") (pinfunction "1_1") (pintype "passive"))
      (node (ref "U12") (pin "96") (pinfunction "RXIN1P_96") (pintype "input"))
    )
    (net (code "111") (name "Net-(U12D-RXIN2N)") (class "Default")
      (node (ref "R125") (pin "2") (pinfunction "2_2") (pintype "passive"))
      (node (ref "U12") (pin "102") (pinfunction "RXIN2N_102") (pintype "input"))
    )
    (net (code "112") (name "Net-(U12D-RXIN2P)") (class "Default")
      (node (ref "R125") (pin "1") (pinfunction "1_1") (pintype "passive"))
      (node (ref "U12") (pin "100") (pinfunction "RXIN2P_100") (pintype "input"))
    )
    (net (code "113") (name "Net-(U12D-RXIN3N)") (class "Default")
      (node (ref "C103") (pin "1") (pinfunction "1_1") (pintype "passive"))
      (node (ref "U12") (pin "110") (pinfunction "RXIN3N_110") (pintype "input"))
    )
    (net (code "114") (name "Net-(U12D-RXIN3P)") (class "Default")
      (node (ref "C102") (pin "1") (pinfunction "1_1") (pintype "passive"))
      (node (ref "U12") (pin "108") (pinfunction "RXIN3P_108") (pintype "input"))
    )
    (net (code "115") (name "Net-(U12D-TXOUT2N)") (class "Default")
      (node (ref "C105") (pin "1") (pinfunction "1_1") (pintype "passive"))
      (node (ref "C96") (pin "1") (pinfunction "1_1") (pintype "passive"))
      (node (ref "L31") (pin "2") (pinfunction "2_2") (pintype "passive"))
      (node (ref "U12") (pin "46") (pinfunction "TXOUT2N_46") (pintype "output"))
    )
    (net (code "116") (name "Net-(U12D-TXOUT2P)") (class "Default")
      (node (ref "C104") (pin "1") (pinfunction "1_1") (pintype "passive"))
      (node (ref "C96") (pin "2") (pinfunction "2_2") (pintype "passive"))
      (node (ref "L30") (pin "2") (pinfunction "2_2") (pintype "passive"))
      (node (ref "U12") (pin "44") (pinfunction "TXOUT2P_44") (pintype "output"))
    )
    (net (code "117") (name "Net-(U14-IN)") (class "Default")
      (node (ref "C101") (pin "2") (pinfunction "2_2") (pintype "passive"))
      (node (ref "U14") (pin "3") (pinfunction "IN_3") (pintype "passive"))
    )
    (net (code "118") (name "Net-(U14-OUT)") (class "Default")
      (node (ref "C110") (pin "1") (pinfunction "1_1") (pintype "passive"))
      (node (ref "L34") (pin "2") (pinfunction "2_2") (pintype "passive"))
      (node (ref "U14") (pin "1") (pinfunction "OUT_1") (pintype "passive"))
    )
    (net (code "119") (name "Net-(U30-ADJ)") (class "Default")
      (node (ref "R96") (pin "2") (pinfunction "2_2") (pintype "passive"))
      (node (ref "R99") (pin "1") (pinfunction "1_1") (pintype "passive"))
      (node (ref "U30") (pin "1") (pinfunction "ADJ_1") (pintype "passive"))
    )
    (net (code "120") (name "Net-(U31-ADJ)") (class "Default")
      (node (ref "R100") (pin "1") (pinfunction "1_1") (pintype "passive"))
      (node (ref "R97") (pin "2") (pinfunction "2_2") (pintype "passive"))
      (node (ref "U31") (pin "1") (pinfunction "ADJ_1") (pintype "passive"))
    )
    (net (code "121") (name "Net-(U32-ADJ)") (class "Default")
      (node (ref "R101") (pin "1") (pinfunction "1_1") (pintype "passive"))
      (node (ref "R98") (pin "2") (pinfunction "2_2") (pintype "passive"))
      (node (ref "U32") (pin "1") (pinfunction "ADJ_1") (pintype "passive"))
    )
    (net (code "122") (name "unconnected-(U12A-PVDDAD33B-Pad12)") (class "Default")
      (node (ref "U12") (pin "12") (pinfunction "PVDDAD33B_12") (pintype "power_in+no_connect"))
    )
    (net (code "123") (name "unconnected-(U12A-PVDDAD33C-Pad18)") (class "Default")
      (node (ref "U12") (pin "18") (pinfunction "PVDDAD33C_18") (pintype "power_in+no_connect"))
    )
    (net (code "124") (name "unconnected-(U12B-RXCLK_OUT-Pad40)") (class "Default")
      (node (ref "U12") (pin "40") (pinfunction "RXCLK_OUT_40") (pintype "output+no_connect"))
    )
    (net (code "125") (name "unconnected-(U12D-IEXMIX1N-Pad94)") (class "Default")
      (node (ref "U12") (pin "94") (pinfunction "IEXMIX1N_94") (pintype "bidirectional+no_connect"))
    )
    (net (code "126") (name "unconnected-(U12D-IEXMIX1P-Pad92)") (class "Default")
      (node (ref "U12") (pin "92") (pinfunction "IEXMIX1P_92") (pintype "bidirectional+no_connect"))
    )
    (net (code "127") (name "unconnected-(U12D-IEXMIX2N-Pad106)") (class "Default")
      (node (ref "U12") (pin "106") (pinfunction "IEXMIX2N_106") (pintype "bidirectional+no_connect"))
    )
    (net (code "128") (name "unconnected-(U12D-IEXMIX2P-Pad104)") (class "Default")
      (node (ref "U12") (pin "104") (pinfunction "IEXMIX2P_104") (pintype "bidirectional+no_connect"))
    )
    (net (code "129") (name "unconnected-(U12D-OEXLNA1N-Pad95)") (class "Default")
      (node (ref "U12") (pin "95") (pinfunction "OEXLNA1N_95") (pintype "bidirectional+no_connect"))
    )
    (net (code "130") (name "unconnected-(U12D-OEXLNA1P-Pad91)") (class "Default")
      (node (ref "U12") (pin "91") (pinfunction "OEXLNA1P_91") (pintype "bidirectional+no_connect"))
    )
    (net (code "131") (name "unconnected-(U12D-OEXLNA2N-Pad105)") (class "Default")
      (node (ref "U12") (pin "105") (pinfunction "OEXLNA2N_105") (pintype "bidirectional+no_connect"))
    )
    (net (code "132") (name "unconnected-(U12D-OEXLNA2P-Pad103)") (class "Default")
      (node (ref "U12") (pin "103") (pinfunction "OEXLNA2P_103") (pintype "bidirectional+no_connect"))
    )
    (net (code "133") (name "unconnected-(U12D-TXOUT1N-Pad50)") (class "Default")
      (node (ref "U12") (pin "50") (pinfunction "TXOUT1N_50") (pintype "output+no_connect"))
    )
    (net (code "134") (name "unconnected-(U12D-TXOUT1P-Pad48)") (class "Default")
      (node (ref "U12") (pin "48") (pinfunction "TXOUT1P_48") (pintype "output+no_connect"))
    )
  )
)
